# attiny45.net
KiCad netlist of a schematic drawn in EAGLE
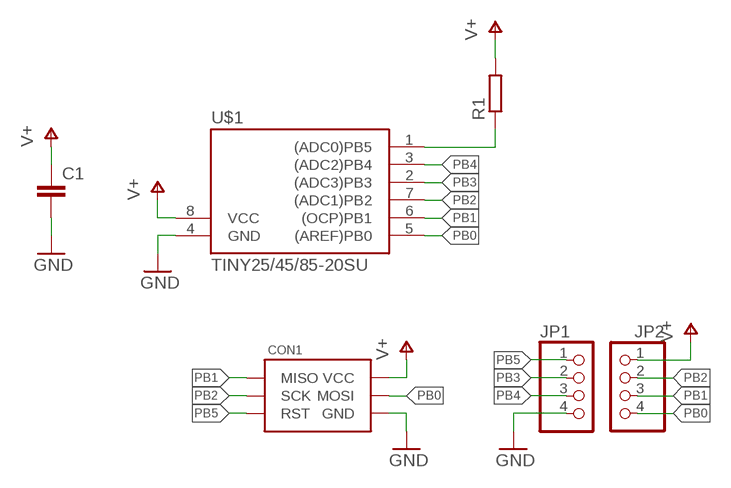
[diagram p0: schematic, sheet 1]

(export (version "E")
  (design (tool "Eeschema 10.0.6"))
  (components
    (comp (ref "C1")
      (value "C-EUC0603")
      (footprint "eagle-import:C0603")
      (libsource (lib "eagle-import") (part "C-EUC0603"))
    )
    (comp (ref "CON1")
      (value "ISP-6_PIN-POGO")
      (footprint "eagle-import:POGO-1.27-6_PIN-MADWORM")
      (libsource (lib "eagle-import") (part "ISP-6_PIN-POGO"))
    )
    (comp (ref "JP1")
      (value "PINHD-1X4")
      (footprint "eagle-import:1X04")
      (libsource (lib "eagle-import") (part "PINHD-1X4"))
    )
    (comp (ref "JP2")
      (value "PINHD-1X4")
      (footprint "eagle-import:1X04")
      (libsource (lib "eagle-import") (part "PINHD-1X4"))
    )
    (comp (ref "R1")
      (value "R-EU_R0603")
      (footprint "eagle-import:R0603")
      (libsource (lib "eagle-import") (part "R-EU_R0603"))
    )
    (comp (ref "U$1")
      (value "TINY25/45/85-20SU")
      (footprint "eagle-import:SOIC8")
      (libsource (lib "eagle-import") (part "TINY25/45/85-20SU"))
    )
  )
  (nets
    (net (code "1") (name "GND") (class "Default")
      (node (ref "C1") (pin "2") (pinfunction "2_2") (pintype "passive"))
      (node (ref "CON1") (pin "P$6") (pinfunction "GND_P$6") (pintype "power_in"))
      (node (ref "JP1") (pin "4") (pinfunction "4_4") (pintype "passive"))
      (node (ref "U$1") (pin "4") (pinfunction "GND_4") (pintype "power_in"))
    )
    (net (code "2") (name "PB0") (class "Default")
      (node (ref "CON1") (pin "P$4") (pinfunction "MOSI_P$4") (pintype "bidirectional"))
      (node (ref "JP2") (pin "4") (pinfunction "4_4") (pintype "passive"))
      (node (ref "U$1") (pin "5") (pinfunction "(AREF)PB0_5") (pintype "bidirectional"))
    )
    (net (code "3") (name "PB1") (class "Default")
      (node (ref "CON1") (pin "P$1") (pinfunction "MISO_P$1") (pintype "bidirectional"))
      (node (ref "JP2") (pin "3") (pinfunction "3_3") (pintype "passive"))
      (node (ref "U$1") (pin "6") (pinfunction "(OCP)PB1_6") (pintype "bidirectional"))
    )
    (net (code "4") (name "PB2") (class "Default")
      (node (ref "CON1") (pin "P$3") (pinfunction "SCK_P$3") (pintype "bidirectional"))
      (node (ref "JP2") (pin "2") (pinfunction "2_2") (pintype "passive"))
      (node (ref "U$1") (pin "7") (pinfunction "(ADC1)PB2_7") (pintype "bidirectional"))
    )
    (net (code "5") (name "PB3") (class "Default")
      (node (ref "JP1") (pin "2") (pinfunction "2_2") (pintype "passive"))
      (node (ref "U$1") (pin "2") (pinfunction "(ADC3)PB3_2") (pintype "bidirectional"))
    )
    (net (code "6") (name "PB4") (class "Default")
      (node (ref "JP1") (pin "3") (pinfunction "3_3") (pintype "passive"))
      (node (ref "U$1") (pin "3") (pinfunction "(ADC2)PB4_3") (pintype "bidirectional"))
    )
    (net (code "7") (name "PB5") (class "Default")
      (node (ref "CON1") (pin "P$5") (pinfunction "RST_P$5") (pintype "bidirectional"))
      (node (ref "JP1") (pin "1") (pinfunction "1_1") (pintype "passive"))
      (node (ref "R1") (pin "1") (pinfunction "1_1") (pintype "passive"))
      (node (ref "U$1") (pin "1") (pinfunction "(ADC0)PB5_1") (pintype "bidirectional"))
    )
    (net (code "8") (name "V+") (class "Default")
      (node (ref "C1") (pin "1") (pinfunction "1_1") (pintype "passive"))
      (node (ref "CON1") (pin "P$2") (pinfunction "VCC_P$2") (pintype "power_in"))
      (node (ref "JP2") (pin "1") (pinfunction "1_1") (pintype "passive"))
      (node (ref "R1") (pin "2") (pinfunction "2_2") (pintype "passive"))
      (node (ref "U$1") (pin "8") (pinfunction "VCC_8") (pintype "power_in"))
    )
  )
)
